# shebon_heart.net
KiCad netlist of a schematic drawn in EAGLE
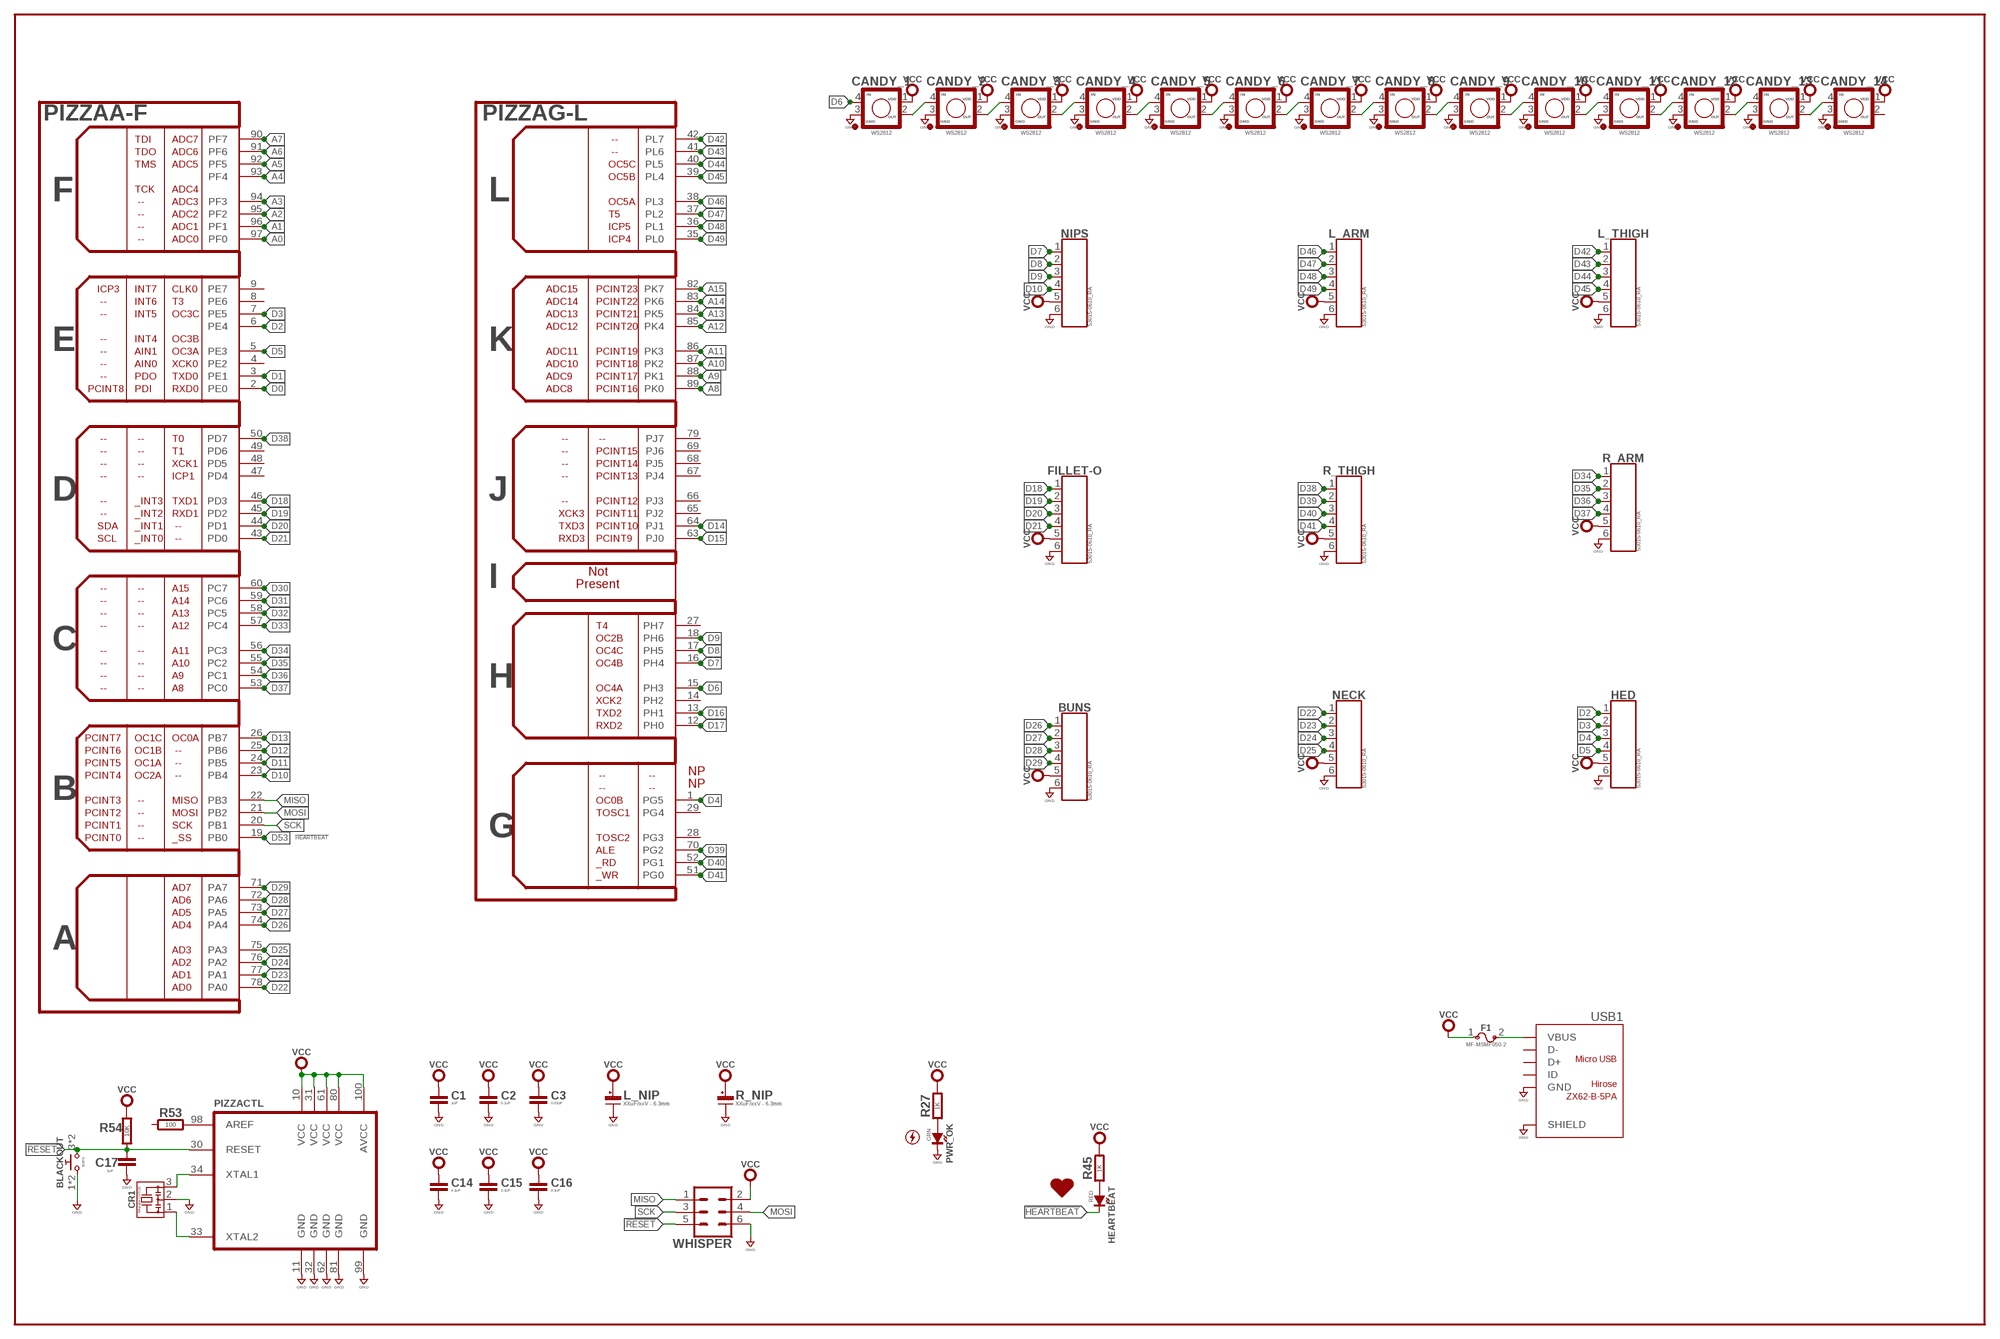
[diagram p0: schematic, sheet 1]

(export (version "E")
  (design (tool "Eeschema 10.0.6"))
  (components
    (comp (ref "BLACKOUT")
      (value "B3FS")
      (footprint "eagle-import:B3FS")
      (libsource (lib "eagle-import") (part "PUSHBTN-MOMB3FS"))
    )
    (comp (ref "BUNS")
      (value "53015-0610_RA")
      (footprint "eagle-import:MICROBLADE-RA-06P")
      (libsource (lib "eagle-import") (part "5301-0610_RA5"))
    )
    (comp (ref "C1")
      (value "1uF")
      (footprint "eagle-import:0603")
      (libsource (lib "eagle-import") (part "CAPACITOR0603"))
    )
    (comp (ref "C2")
      (value "0.1uF")
      (footprint "eagle-import:0603")
      (libsource (lib "eagle-import") (part "CAPACITOR0603"))
    )
    (comp (ref "C3")
      (value "0.01uF")
      (footprint "eagle-import:0603")
      (libsource (lib "eagle-import") (part "CAPACITOR0603"))
    )
    (comp (ref "C14")
      (value "0.1uF")
      (footprint "eagle-import:0603")
      (libsource (lib "eagle-import") (part "CAPACITOR0603"))
    )
    (comp (ref "C15")
      (value "0.1uF")
      (footprint "eagle-import:0603")
      (libsource (lib "eagle-import") (part "CAPACITOR0603"))
    )
    (comp (ref "C16")
      (value "0.1uF")
      (footprint "eagle-import:0603")
      (libsource (lib "eagle-import") (part "CAPACITOR0603"))
    )
    (comp (ref "C17")
      (value "1uF")
      (footprint "eagle-import:0603")
      (libsource (lib "eagle-import") (part "CAPACITOR0603"))
    )
    (comp (ref "CANDY_1")
      (value "WS2812")
      (footprint "eagle-import:NEOPIXEL")
      (libsource (lib "eagle-import") (part "NEOPPIXEL5X5"))
    )
    (comp (ref "CANDY_2")
      (value "WS2812")
      (footprint "eagle-import:NEOPIXEL")
      (libsource (lib "eagle-import") (part "NEOPPIXEL5X5"))
    )
    (comp (ref "CANDY_3")
      (value "WS2812")
      (footprint "eagle-import:NEOPIXEL")
      (libsource (lib "eagle-import") (part "NEOPPIXEL5X5"))
    )
    (comp (ref "CANDY_4")
      (value "WS2812")
      (footprint "eagle-import:NEOPIXEL")
      (libsource (lib "eagle-import") (part "NEOPPIXEL5X5"))
    )
    (comp (ref "CANDY_5")
      (value "WS2812")
      (footprint "eagle-import:NEOPIXEL")
      (libsource (lib "eagle-import") (part "NEOPPIXEL5X5"))
    )
    (comp (ref "CANDY_6")
      (value "WS2812")
      (footprint "eagle-import:NEOPIXEL")
      (libsource (lib "eagle-import") (part "NEOPPIXEL5X5"))
    )
    (comp (ref "CANDY_7")
      (value "WS2812")
      (footprint "eagle-import:NEOPIXEL")
      (libsource (lib "eagle-import") (part "NEOPPIXEL5X5"))
    )
    (comp (ref "CANDY_8")
      (value "WS2812")
      (footprint "eagle-import:NEOPIXEL")
      (libsource (lib "eagle-import") (part "NEOPPIXEL5X5"))
    )
    (comp (ref "CANDY_9")
      (value "WS2812")
      (footprint "eagle-import:NEOPIXEL")
      (libsource (lib "eagle-import") (part "NEOPPIXEL5X5"))
    )
    (comp (ref "CANDY_10")
      (value "WS2812")
      (footprint "eagle-import:NEOPIXEL")
      (libsource (lib "eagle-import") (part "NEOPPIXEL5X5"))
    )
    (comp (ref "CANDY_11")
      (value "WS2812")
      (footprint "eagle-import:NEOPIXEL")
      (libsource (lib "eagle-import") (part "NEOPPIXEL5X5"))
    )
    (comp (ref "CANDY_12")
      (value "WS2812")
      (footprint "eagle-import:NEOPIXEL")
      (libsource (lib "eagle-import") (part "NEOPPIXEL5X5"))
    )
    (comp (ref "CANDY_13")
      (value "WS2812")
      (footprint "eagle-import:NEOPIXEL")
      (libsource (lib "eagle-import") (part "NEOPPIXEL5X5"))
    )
    (comp (ref "CANDY_14")
      (value "WS2812")
      (footprint "eagle-import:NEOPIXEL")
      (libsource (lib "eagle-import") (part "NEOPPIXEL5X5"))
    )
    (comp (ref "CR1")
      (value "Murata CSTCE")
      (footprint "eagle-import:MURATA_CSTCE")
      (libsource (lib "eagle-import") (part "RESONATORMURATA-CSTCE"))
    )
    (comp (ref "F1")
      (value "MF-MSMF050-2")
      (footprint "eagle-import:BOURNS-MF-MSMF")
      (libsource (lib "eagle-import") (part "FUSEBOURNS-MF-MSMF"))
    )
    (comp (ref "FILLET-O")
      (value "53015-0610_RA")
      (footprint "eagle-import:MICROBLADE-RA-06P")
      (libsource (lib "eagle-import") (part "5301-0610_RA5"))
    )
    (comp (ref "HEARTBEAT")
      (value "RED")
      (footprint "eagle-import:SMD_0603")
      (libsource (lib "eagle-import") (part "SMT0603"))
    )
    (comp (ref "HED")
      (value "53015-0610_RA")
      (footprint "eagle-import:MICROBLADE-RA-06P")
      (libsource (lib "eagle-import") (part "5301-0610_RA5"))
    )
    (comp (ref "L_ARM")
      (value "53015-0610_RA")
      (footprint "eagle-import:MICROBLADE-RA-06P")
      (libsource (lib "eagle-import") (part "5301-0610_RA5"))
    )
    (comp (ref "L_NIP")
      (value "XXuF/xxV - 6.3mm")
      (footprint "eagle-import:CAP_ALUM_SMT_6.3")
      (libsource (lib "eagle-import") (part "CAPACITOR_POL-ALUM-SMT-6.3"))
    )
    (comp (ref "L_THIGH")
      (value "53015-0610_RA")
      (footprint "eagle-import:MICROBLADE-RA-06P")
      (libsource (lib "eagle-import") (part "5301-0610_RA5"))
    )
    (comp (ref "NECK")
      (value "53015-0610_RA")
      (footprint "eagle-import:MICROBLADE-RA-06P")
      (libsource (lib "eagle-import") (part "5301-0610_RA5"))
    )
    (comp (ref "NIPS")
      (value "53015-0610_RA")
      (footprint "eagle-import:MICROBLADE-RA-06P")
      (libsource (lib "eagle-import") (part "5301-0610_RA5"))
    )
    (comp (ref "PIZZA")
      (value "ATMEGA-2560")
      (footprint "eagle-import:TQFP-100-A")
      (libsource (lib "eagle-import") (part "ATMEGA-0256"))
    )
    (comp (ref "PWR_OK")
      (value "GRN")
      (footprint "eagle-import:SMD_0603")
      (libsource (lib "eagle-import") (part "SMT0603"))
    )
    (comp (ref "R27")
      (value "1K")
      (footprint "eagle-import:0603")
      (libsource (lib "eagle-import") (part "RESISTOR0603"))
    )
    (comp (ref "R45")
      (value "1K")
      (footprint "eagle-import:0603")
      (libsource (lib "eagle-import") (part "RESISTOR0603"))
    )
    (comp (ref "R53")
      (value "100")
      (footprint "eagle-import:0603")
      (libsource (lib "eagle-import") (part "RESISTOR0603"))
    )
    (comp (ref "R54")
      (value "10K")
      (footprint "eagle-import:0603")
      (libsource (lib "eagle-import") (part "RESISTOR0603"))
    )
    (comp (ref "R_ARM")
      (value "53015-0610_RA")
      (footprint "eagle-import:MICROBLADE-RA-06P")
      (libsource (lib "eagle-import") (part "5301-0610_RA5"))
    )
    (comp (ref "R_NIP")
      (value "XXuF/xxV - 6.3mm")
      (footprint "eagle-import:CAP_ALUM_SMT_6.3")
      (libsource (lib "eagle-import") (part "CAPACITOR_POL-ALUM-SMT-6.3"))
    )
    (comp (ref "R_THIGH")
      (value "53015-0610_RA")
      (footprint "eagle-import:MICROBLADE-RA-06P")
      (libsource (lib "eagle-import") (part "5301-0610_RA5"))
    )
    (comp (ref "U$2")
      (value "ELECTRICITY-050X050MM")
      (footprint "eagle-import:ELECTRICITY-GLYPH-05X05MM")
      (libsource (lib "eagle-import") (part "ELECTRICITY-050X050MM"))
    )
    (comp (ref "U$3")
      (value "HEART-05X04MM")
      (footprint "eagle-import:HEART-GLYPH-05X04MM")
      (libsource (lib "eagle-import") (part "HEART-05X04MM"))
    )
    (comp (ref "USB1")
      (value "ZX62-B-5PA")
      (footprint "eagle-import:MICRO-USB5+6P-SMD-0.65-AB")
      (libsource (lib "eagle-import") (part "MICRO-USB-SMD(ZX62-B-5PA)"))
    )
    (comp (ref "WHISPER")
      (value "MA03-2")
      (footprint "eagle-import:MA03-2")
      (libsource (lib "eagle-import") (part "MA03-2"))
    )
  )
  (nets
    (net (code "1") (name "/~{HEARTBEAT}") (class "Default")
      (node (ref "HEARTBEAT") (pin "K") (pinfunction "C_K") (pintype "passive"))
    )
    (net (code "2") (name "/~{RESET}") (class "Default")
      (node (ref "BLACKOUT") (pin "3") (pinfunction "2_3") (pintype "passive"))
      (node (ref "BLACKOUT") (pin "4") (pinfunction "2_4") (pintype "passive"))
      (node (ref "C17") (pin "1") (pinfunction "1_1") (pintype "passive"))
      (node (ref "PIZZA") (pin "30") (pinfunction "RESET_30") (pintype "input"))
      (node (ref "R54") (pin "2") (pinfunction "2_2") (pintype "passive"))
      (node (ref "WHISPER") (pin "5") (pinfunction "5_5") (pintype "passive"))
    )
    (net (code "3") (name "A0") (class "Default")
      (node (ref "PIZZA") (pin "97") (pinfunction "PF0_97") (pintype "bidirectional"))
    )
    (net (code "4") (name "A1") (class "Default")
      (node (ref "PIZZA") (pin "96") (pinfunction "PF1_96") (pintype "bidirectional"))
    )
    (net (code "5") (name "A2") (class "Default")
      (node (ref "PIZZA") (pin "95") (pinfunction "PF2_95") (pintype "bidirectional"))
    )
    (net (code "6") (name "A3") (class "Default")
      (node (ref "PIZZA") (pin "94") (pinfunction "PF3_94") (pintype "bidirectional"))
    )
    (net (code "7") (name "A4") (class "Default")
      (node (ref "PIZZA") (pin "93") (pinfunction "PF4_93") (pintype "bidirectional"))
    )
    (net (code "8") (name "A5") (class "Default")
      (node (ref "PIZZA") (pin "92") (pinfunction "PF5_92") (pintype "bidirectional"))
    )
    (net (code "9") (name "A6") (class "Default")
      (node (ref "PIZZA") (pin "91") (pinfunction "PF6_91") (pintype "bidirectional"))
    )
    (net (code "10") (name "A7") (class "Default")
      (node (ref "PIZZA") (pin "90") (pinfunction "PF7_90") (pintype "bidirectional"))
    )
    (net (code "11") (name "A8") (class "Default")
      (node (ref "PIZZA") (pin "89") (pinfunction "PK0_89") (pintype "bidirectional"))
    )
    (net (code "12") (name "A9") (class "Default")
      (node (ref "PIZZA") (pin "88") (pinfunction "PK1_88") (pintype "bidirectional"))
    )
    (net (code "13") (name "A10") (class "Default")
      (node (ref "PIZZA") (pin "87") (pinfunction "PK2_87") (pintype "bidirectional"))
    )
    (net (code "14") (name "A11") (class "Default")
      (node (ref "PIZZA") (pin "86") (pinfunction "PK3_86") (pintype "bidirectional"))
    )
    (net (code "15") (name "A12") (class "Default")
      (node (ref "PIZZA") (pin "85") (pinfunction "PK4_85") (pintype "bidirectional"))
    )
    (net (code "16") (name "A13") (class "Default")
      (node (ref "PIZZA") (pin "84") (pinfunction "PK5_84") (pintype "bidirectional"))
    )
    (net (code "17") (name "A14") (class "Default")
      (node (ref "PIZZA") (pin "83") (pinfunction "PK6_83") (pintype "bidirectional"))
    )
    (net (code "18") (name "A15") (class "Default")
      (node (ref "PIZZA") (pin "82") (pinfunction "PK7_82") (pintype "bidirectional"))
    )
    (net (code "19") (name "D0") (class "Default")
      (node (ref "PIZZA") (pin "2") (pinfunction "PE0_2") (pintype "bidirectional"))
    )
    (net (code "20") (name "D1") (class "Default")
      (node (ref "PIZZA") (pin "3") (pinfunction "PE1_3") (pintype "bidirectional"))
    )
    (net (code "21") (name "D2") (class "Default")
      (node (ref "HED") (pin "1") (pinfunction "1_1") (pintype "bidirectional"))
      (node (ref "PIZZA") (pin "6") (pinfunction "PE4_6") (pintype "bidirectional"))
    )
    (net (code "22") (name "D3") (class "Default")
      (node (ref "HED") (pin "2") (pinfunction "2_2") (pintype "bidirectional"))
      (node (ref "PIZZA") (pin "7") (pinfunction "PE5_7") (pintype "bidirectional"))
    )
    (net (code "23") (name "D4") (class "Default")
      (node (ref "HED") (pin "3") (pinfunction "3_3") (pintype "bidirectional"))
      (node (ref "PIZZA") (pin "1") (pinfunction "PG5_1") (pintype "bidirectional"))
    )
    (net (code "24") (name "D5") (class "Default")
      (node (ref "HED") (pin "4") (pinfunction "4_4") (pintype "bidirectional"))
      (node (ref "PIZZA") (pin "5") (pinfunction "PE3_5") (pintype "bidirectional"))
    )
    (net (code "25") (name "D6") (class "Default")
      (node (ref "CANDY_1") (pin "4") (pinfunction "OUT_4") (pintype "bidirectional"))
      (node (ref "PIZZA") (pin "15") (pinfunction "PH3_15") (pintype "bidirectional"))
    )
    (net (code "26") (name "D7") (class "Default")
      (node (ref "NIPS") (pin "1") (pinfunction "1_1") (pintype "bidirectional"))
      (node (ref "PIZZA") (pin "16") (pinfunction "PH4_16") (pintype "bidirectional"))
    )
    (net (code "27") (name "D8") (class "Default")
      (node (ref "NIPS") (pin "2") (pinfunction "2_2") (pintype "bidirectional"))
      (node (ref "PIZZA") (pin "17") (pinfunction "PH5_17") (pintype "bidirectional"))
    )
    (net (code "28") (name "D9") (class "Default")
      (node (ref "NIPS") (pin "3") (pinfunction "3_3") (pintype "bidirectional"))
      (node (ref "PIZZA") (pin "18") (pinfunction "PH6_18") (pintype "bidirectional"))
    )
    (net (code "29") (name "D10") (class "Default")
      (node (ref "NIPS") (pin "4") (pinfunction "4_4") (pintype "bidirectional"))
      (node (ref "PIZZA") (pin "23") (pinfunction "PB4_23") (pintype "bidirectional"))
    )
    (net (code "30") (name "D11") (class "Default")
      (node (ref "PIZZA") (pin "24") (pinfunction "PB5_24") (pintype "bidirectional"))
    )
    (net (code "31") (name "D12") (class "Default")
      (node (ref "PIZZA") (pin "25") (pinfunction "PB6_25") (pintype "bidirectional"))
    )
    (net (code "32") (name "D13") (class "Default")
      (node (ref "PIZZA") (pin "26") (pinfunction "PB7_26") (pintype "bidirectional"))
    )
    (net (code "33") (name "D14") (class "Default")
      (node (ref "PIZZA") (pin "64") (pinfunction "PJ1_64") (pintype "bidirectional"))
    )
    (net (code "34") (name "D15") (class "Default")
      (node (ref "PIZZA") (pin "63") (pinfunction "PJ0_63") (pintype "bidirectional"))
    )
    (net (code "35") (name "D16") (class "Default")
      (node (ref "PIZZA") (pin "13") (pinfunction "PH1_13") (pintype "bidirectional"))
    )
    (net (code "36") (name "D17") (class "Default")
      (node (ref "PIZZA") (pin "12") (pinfunction "PH0_12") (pintype "bidirectional"))
    )
    (net (code "37") (name "D18") (class "Default")
      (node (ref "FILLET-O") (pin "1") (pinfunction "1_1") (pintype "bidirectional"))
      (node (ref "PIZZA") (pin "46") (pinfunction "PD3_46") (pintype "bidirectional"))
    )
    (net (code "38") (name "D19") (class "Default")
      (node (ref "FILLET-O") (pin "2") (pinfunction "2_2") (pintype "bidirectional"))
      (node (ref "PIZZA") (pin "45") (pinfunction "PD2_45") (pintype "bidirectional"))
    )
    (net (code "39") (name "D20") (class "Default")
      (node (ref "FILLET-O") (pin "3") (pinfunction "3_3") (pintype "bidirectional"))
      (node (ref "PIZZA") (pin "44") (pinfunction "PD1_44") (pintype "bidirectional"))
    )
    (net (code "40") (name "D21") (class "Default")
      (node (ref "FILLET-O") (pin "4") (pinfunction "4_4") (pintype "bidirectional"))
      (node (ref "PIZZA") (pin "43") (pinfunction "PD0_43") (pintype "bidirectional"))
    )
    (net (code "41") (name "D22") (class "Default")
      (node (ref "NECK") (pin "1") (pinfunction "1_1") (pintype "bidirectional"))
      (node (ref "PIZZA") (pin "78") (pinfunction "PA0_78") (pintype "bidirectional"))
    )
    (net (code "42") (name "D23") (class "Default")
      (node (ref "NECK") (pin "2") (pinfunction "2_2") (pintype "bidirectional"))
      (node (ref "PIZZA") (pin "77") (pinfunction "PA1_77") (pintype "bidirectional"))
    )
    (net (code "43") (name "D24") (class "Default")
      (node (ref "NECK") (pin "3") (pinfunction "3_3") (pintype "bidirectional"))
      (node (ref "PIZZA") (pin "76") (pinfunction "PA2_76") (pintype "bidirectional"))
    )
    (net (code "44") (name "D25") (class "Default")
      (node (ref "NECK") (pin "4") (pinfunction "4_4") (pintype "bidirectional"))
      (node (ref "PIZZA") (pin "75") (pinfunction "PA3_75") (pintype "bidirectional"))
    )
    (net (code "45") (name "D26") (class "Default")
      (node (ref "BUNS") (pin "1") (pinfunction "1_1") (pintype "bidirectional"))
      (node (ref "PIZZA") (pin "74") (pinfunction "PA4_74") (pintype "bidirectional"))
    )
    (net (code "46") (name "D27") (class "Default")
      (node (ref "BUNS") (pin "2") (pinfunction "2_2") (pintype "bidirectional"))
      (node (ref "PIZZA") (pin "73") (pinfunction "PA5_73") (pintype "bidirectional"))
    )
    (net (code "47") (name "D28") (class "Default")
      (node (ref "BUNS") (pin "3") (pinfunction "3_3") (pintype "bidirectional"))
      (node (ref "PIZZA") (pin "72") (pinfunction "PA6_72") (pintype "bidirectional"))
    )
    (net (code "48") (name "D29") (class "Default")
      (node (ref "BUNS") (pin "4") (pinfunction "4_4") (pintype "bidirectional"))
      (node (ref "PIZZA") (pin "71") (pinfunction "PA7_71") (pintype "bidirectional"))
    )
    (net (code "49") (name "D30") (class "Default")
      (node (ref "PIZZA") (pin "60") (pinfunction "PC7_60") (pintype "bidirectional"))
    )
    (net (code "50") (name "D31") (class "Default")
      (node (ref "PIZZA") (pin "59") (pinfunction "PC6_59") (pintype "bidirectional"))
    )
    (net (code "51") (name "D32") (class "Default")
      (node (ref "PIZZA") (pin "58") (pinfunction "PC5_58") (pintype "bidirectional"))
    )
    (net (code "52") (name "D33") (class "Default")
      (node (ref "PIZZA") (pin "57") (pinfunction "PC4_57") (pintype "bidirectional"))
    )
    (net (code "53") (name "D34") (class "Default")
      (node (ref "PIZZA") (pin "56") (pinfunction "PC3_56") (pintype "bidirectional"))
      (node (ref "R_ARM") (pin "1") (pinfunction "1_1") (pintype "bidirectional"))
    )
    (net (code "54") (name "D35") (class "Default")
      (node (ref "PIZZA") (pin "55") (pinfunction "PC2_55") (pintype "bidirectional"))
      (node (ref "R_ARM") (pin "2") (pinfunction "2_2") (pintype "bidirectional"))
    )
    (net (code "55") (name "D36") (class "Default")
      (node (ref "PIZZA") (pin "54") (pinfunction "PC1_54") (pintype "bidirectional"))
      (node (ref "R_ARM") (pin "3") (pinfunction "3_3") (pintype "bidirectional"))
    )
    (net (code "56") (name "D37") (class "Default")
      (node (ref "PIZZA") (pin "53") (pinfunction "PC0_53") (pintype "bidirectional"))
      (node (ref "R_ARM") (pin "4") (pinfunction "4_4") (pintype "bidirectional"))
    )
    (net (code "57") (name "D38") (class "Default")
      (node (ref "PIZZA") (pin "50") (pinfunction "PD7_50") (pintype "bidirectional"))
      (node (ref "R_THIGH") (pin "1") (pinfunction "1_1") (pintype "bidirectional"))
    )
    (net (code "58") (name "D39") (class "Default")
      (node (ref "PIZZA") (pin "70") (pinfunction "PG2_70") (pintype "bidirectional"))
      (node (ref "R_THIGH") (pin "2") (pinfunction "2_2") (pintype "bidirectional"))
    )
    (net (code "59") (name "D40") (class "Default")
      (node (ref "PIZZA") (pin "52") (pinfunction "PG1_52") (pintype "bidirectional"))
      (node (ref "R_THIGH") (pin "3") (pinfunction "3_3") (pintype "bidirectional"))
    )
    (net (code "60") (name "D41") (class "Default")
      (node (ref "PIZZA") (pin "51") (pinfunction "PG0_51") (pintype "bidirectional"))
      (node (ref "R_THIGH") (pin "4") (pinfunction "4_4") (pintype "bidirectional"))
    )
    (net (code "61") (name "D42") (class "Default")
      (node (ref "L_THIGH") (pin "1") (pinfunction "1_1") (pintype "bidirectional"))
      (node (ref "PIZZA") (pin "42") (pinfunction "PL7_42") (pintype "bidirectional"))
    )
    (net (code "62") (name "D43") (class "Default")
      (node (ref "L_THIGH") (pin "2") (pinfunction "2_2") (pintype "bidirectional"))
      (node (ref "PIZZA") (pin "41") (pinfunction "PL6_41") (pintype "bidirectional"))
    )
    (net (code "63") (name "D44") (class "Default")
      (node (ref "L_THIGH") (pin "3") (pinfunction "3_3") (pintype "bidirectional"))
      (node (ref "PIZZA") (pin "40") (pinfunction "PL5_40") (pintype "bidirectional"))
    )
    (net (code "64") (name "D45") (class "Default")
      (node (ref "L_THIGH") (pin "4") (pinfunction "4_4") (pintype "bidirectional"))
      (node (ref "PIZZA") (pin "39") (pinfunction "PL4_39") (pintype "bidirectional"))
    )
    (net (code "65") (name "D46") (class "Default")
      (node (ref "L_ARM") (pin "1") (pinfunction "1_1") (pintype "bidirectional"))
      (node (ref "PIZZA") (pin "38") (pinfunction "PL3_38") (pintype "bidirectional"))
    )
    (net (code "66") (name "D47") (class "Default")
      (node (ref "L_ARM") (pin "2") (pinfunction "2_2") (pintype "bidirectional"))
      (node (ref "PIZZA") (pin "37") (pinfunction "PL2_37") (pintype "bidirectional"))
    )
    (net (code "67") (name "D48") (class "Default")
      (node (ref "L_ARM") (pin "3") (pinfunction "3_3") (pintype "bidirectional"))
      (node (ref "PIZZA") (pin "36") (pinfunction "PL1_36") (pintype "bidirectional"))
    )
    (net (code "68") (name "D49") (class "Default")
      (node (ref "L_ARM") (pin "4") (pinfunction "4_4") (pintype "bidirectional"))
      (node (ref "PIZZA") (pin "35") (pinfunction "PL0_35") (pintype "bidirectional"))
    )
    (net (code "69") (name "D53") (class "Default")
      (node (ref "PIZZA") (pin "19") (pinfunction "PB0_19") (pintype "bidirectional"))
    )
    (net (code "70") (name "GND") (class "Default")
      (node (ref "BLACKOUT") (pin "1") (pinfunction "1_1") (pintype "passive"))
      (node (ref "BLACKOUT") (pin "2") (pinfunction "1_2") (pintype "passive"))
      (node (ref "BUNS") (pin "6") (pinfunction "6_6") (pintype "bidirectional"))
      (node (ref "C1") (pin "2") (pinfunction "2_2") (pintype "passive"))
      (node (ref "C14") (pin "2") (pinfunction "2_2") (pintype "passive"))
      (node (ref "C15") (pin "2") (pinfunction "2_2") (pintype "passive"))
      (node (ref "C16") (pin "2") (pinfunction "2_2") (pintype "passive"))
      (node (ref "C17") (pin "2") (pinfunction "2_2") (pintype "passive"))
      (node (ref "C2") (pin "2") (pinfunction "2_2") (pintype "passive"))
      (node (ref "C3") (pin "2") (pinfunction "2_2") (pintype "passive"))
      (node (ref "CANDY_1") (pin "3") (pinfunction "GND_3") (pintype "bidirectional"))
      (node (ref "CANDY_10") (pin "3") (pinfunction "GND_3") (pintype "bidirectional"))
      (node (ref "CANDY_11") (pin "3") (pinfunction "GND_3") (pintype "bidirectional"))
      (node (ref "CANDY_12") (pin "3") (pinfunction "GND_3") (pintype "bidirectional"))
      (node (ref "CANDY_13") (pin "3") (pinfunction "GND_3") (pintype "bidirectional"))
      (node (ref "CANDY_14") (pin "3") (pinfunction "GND_3") (pintype "bidirectional"))
      (node (ref "CANDY_2") (pin "3") (pinfunction "GND_3") (pintype "bidirectional"))
      (node (ref "CANDY_3") (pin "3") (pinfunction "GND_3") (pintype "bidirectional"))
      (node (ref "CANDY_4") (pin "3") (pinfunction "GND_3") (pintype "bidirectional"))
      (node (ref "CANDY_5") (pin "3") (pinfunction "GND_3") (pintype "bidirectional"))
      (node (ref "CANDY_6") (pin "3") (pinfunction "GND_3") (pintype "bidirectional"))
      (node (ref "CANDY_7") (pin "3") (pinfunction "GND_3") (pintype "bidirectional"))
      (node (ref "CANDY_8") (pin "3") (pinfunction "GND_3") (pintype "bidirectional"))
      (node (ref "CANDY_9") (pin "3") (pinfunction "GND_3") (pintype "bidirectional"))
      (node (ref "CR1") (pin "2") (pinfunction "2_2") (pintype "bidirectional"))
      (node (ref "FILLET-O") (pin "6") (pinfunction "6_6") (pintype "bidirectional"))
      (node (ref "HED") (pin "6") (pinfunction "6_6") (pintype "bidirectional"))
      (node (ref "L_ARM") (pin "6") (pinfunction "6_6") (pintype "bidirectional"))
      (node (ref "L_NIP") (pin "-") (pinfunction "N_-") (pintype "bidirectional"))
      (node (ref "L_THIGH") (pin "6") (pinfunction "6_6") (pintype "bidirectional"))
      (node (ref "NECK") (pin "6") (pinfunction "6_6") (pintype "bidirectional"))
      (node (ref "NIPS") (pin "6") (pinfunction "6_6") (pintype "bidirectional"))
      (node (ref "PIZZA") (pin "11") (pinfunction "GND_11") (pintype "power_in"))
      (node (ref "PIZZA") (pin "32") (pinfunction "GND_32") (pintype "power_in"))
      (node (ref "PIZZA") (pin "62") (pinfunction "GND_62") (pintype "power_in"))
      (node (ref "PIZZA") (pin "81") (pinfunction "GND_81") (pintype "power_in"))
      (node (ref "PIZZA") (pin "99") (pinfunction "GND_99") (pintype "power_in"))
      (node (ref "PWR_OK") (pin "K") (pinfunction "C_K") (pintype "passive"))
      (node (ref "R_ARM") (pin "6") (pinfunction "6_6") (pintype "bidirectional"))
      (node (ref "R_NIP") (pin "-") (pinfunction "N_-") (pintype "bidirectional"))
      (node (ref "R_THIGH") (pin "6") (pinfunction "6_6") (pintype "bidirectional"))
      (node (ref "USB1") (pin "5") (pinfunction "GND_5") (pintype "power_in"))
      (node (ref "USB1") (pin "P1") (pinfunction "SHIELD_P1") (pintype "power_in"))
      (node (ref "USB1") (pin "P2") (pinfunction "SHIELD_P2") (pintype "power_in"))
      (node (ref "USB1") (pin "P3_1") (pinfunction "SHIELD_P3_1") (pintype "power_in"))
      (node (ref "USB1") (pin "P3_2") (pinfunction "SHIELD_P3_2") (pintype "power_in"))
      (node (ref "USB1") (pin "P3_3") (pinfunction "SHIELD_P3_3") (pintype "power_in"))
      (node (ref "USB1") (pin "P4_1") (pinfunction "SHIELD_P4_1") (pintype "power_in"))
      (node (ref "USB1") (pin "P4_2") (pinfunction "SHIELD_P4_2") (pintype "power_in"))
      (node (ref "USB1") (pin "P4_3") (pinfunction "SHIELD_P4_3") (pintype "power_in"))
      (node (ref "USB1") (pin "P5") (pinfunction "SHIELD_P5") (pintype "power_in"))
      (node (ref "USB1") (pin "P6") (pinfunction "SHIELD_P6") (pintype "power_in"))
      (node (ref "WHISPER") (pin "6") (pinfunction "6_6") (pintype "passive"))
    )
    (net (code "71") (name "MISO") (class "Default")
      (node (ref "PIZZA") (pin "22") (pinfunction "PB3_22") (pintype "bidirectional"))
      (node (ref "WHISPER") (pin "1") (pinfunction "1_1") (pintype "passive"))
    )
    (net (code "72") (name "MOSI") (class "Default")
      (node (ref "PIZZA") (pin "21") (pinfunction "PB2_21") (pintype "bidirectional"))
      (node (ref "WHISPER") (pin "4") (pinfunction "4_4") (pintype "passive"))
    )
    (net (code "73") (name "Net-(CANDY_1-IN)") (class "Default")
      (node (ref "CANDY_1") (pin "2") (pinfunction "IN_2") (pintype "bidirectional"))
      (node (ref "CANDY_2") (pin "4") (pinfunction "OUT_4") (pintype "bidirectional"))
    )
    (net (code "74") (name "Net-(CANDY_2-IN)") (class "Default")
      (node (ref "CANDY_2") (pin "2") (pinfunction "IN_2") (pintype "bidirectional"))
      (node (ref "CANDY_3") (pin "4") (pinfunction "OUT_4") (pintype "bidirectional"))
    )
    (net (code "75") (name "Net-(CANDY_3-IN)") (class "Default")
      (node (ref "CANDY_3") (pin "2") (pinfunction "IN_2") (pintype "bidirectional"))
      (node (ref "CANDY_4") (pin "4") (pinfunction "OUT_4") (pintype "bidirectional"))
    )
    (net (code "76") (name "Net-(CANDY_4-IN)") (class "Default")
      (node (ref "CANDY_4") (pin "2") (pinfunction "IN_2") (pintype "bidirectional"))
      (node (ref "CANDY_5") (pin "4") (pinfunction "OUT_4") (pintype "bidirectional"))
    )
    (net (code "77") (name "Net-(CANDY_5-IN)") (class "Default")
      (node (ref "CANDY_5") (pin "2") (pinfunction "IN_2") (pintype "bidirectional"))
      (node (ref "CANDY_6") (pin "4") (pinfunction "OUT_4") (pintype "bidirectional"))
    )
    (net (code "78") (name "Net-(CANDY_6-IN)") (class "Default")
      (node (ref "CANDY_6") (pin "2") (pinfunction "IN_2") (pintype "bidirectional"))
      (node (ref "CANDY_7") (pin "4") (pinfunction "OUT_4") (pintype "bidirectional"))
    )
    (net (code "79") (name "Net-(CANDY_7-IN)") (class "Default")
      (node (ref "CANDY_7") (pin "2") (pinfunction "IN_2") (pintype "bidirectional"))
      (node (ref "CANDY_8") (pin "4") (pinfunction "OUT_4") (pintype "bidirectional"))
    )
    (net (code "80") (name "Net-(CANDY_8-IN)") (class "Default")
      (node (ref "CANDY_8") (pin "2") (pinfunction "IN_2") (pintype "bidirectional"))
      (node (ref "CANDY_9") (pin "4") (pinfunction "OUT_4") (pintype "bidirectional"))
    )
    (net (code "81") (name "Net-(CANDY_10-IN)") (class "Default")
      (node (ref "CANDY_10") (pin "2") (pinfunction "IN_2") (pintype "bidirectional"))
      (node (ref "CANDY_11") (pin "4") (pinfunction "OUT_4") (pintype "bidirectional"))
    )
    (net (code "82") (name "Net-(CANDY_10-OUT)") (class "Default")
      (node (ref "CANDY_10") (pin "4") (pinfunction "OUT_4") (pintype "bidirectional"))
      (node (ref "CANDY_9") (pin "2") (pinfunction "IN_2") (pintype "bidirectional"))
    )
    (net (code "83") (name "Net-(CANDY_11-IN)") (class "Default")
      (node (ref "CANDY_11") (pin "2") (pinfunction "IN_2") (pintype "bidirectional"))
      (node (ref "CANDY_12") (pin "4") (pinfunction "OUT_4") (pintype "bidirectional"))
    )
    (net (code "84") (name "Net-(CANDY_12-IN)") (class "Default")
      (node (ref "CANDY_12") (pin "2") (pinfunction "IN_2") (pintype "bidirectional"))
      (node (ref "CANDY_13") (pin "4") (pinfunction "OUT_4") (pintype "bidirectional"))
    )
    (net (code "85") (name "Net-(CANDY_13-IN)") (class "Default")
      (node (ref "CANDY_13") (pin "2") (pinfunction "IN_2") (pintype "bidirectional"))
      (node (ref "CANDY_14") (pin "4") (pinfunction "OUT_4") (pintype "bidirectional"))
    )
    (net (code "86") (name "Net-(HEARTBEAT-PadA)") (class "Default")
      (node (ref "HEARTBEAT") (pin "A") (pinfunction "A_A") (pintype "passive"))
      (node (ref "R45") (pin "1") (pinfunction "1_1") (pintype "passive"))
    )
    (net (code "87") (name "Net-(PIZZAB-AREF)") (class "Default")
      (node (ref "PIZZA") (pin "98") (pinfunction "AREF_98") (pintype "input"))
      (node (ref "R53") (pin "2") (pinfunction "2_2") (pintype "passive"))
    )
    (net (code "88") (name "Net-(PIZZAB-XTAL1)") (class "Default")
      (node (ref "CR1") (pin "3") (pinfunction "3_3") (pintype "bidirectional"))
      (node (ref "PIZZA") (pin "34") (pinfunction "XTAL1_34") (pintype "passive"))
    )
    (net (code "89") (name "Net-(PIZZAB-XTAL2)") (class "Default")
      (node (ref "CR1") (pin "1") (pinfunction "1_1") (pintype "bidirectional"))
      (node (ref "PIZZA") (pin "33") (pinfunction "XTAL2_33") (pintype "passive"))
    )
    (net (code "90") (name "Net-(PWR_OK-PadA)") (class "Default")
      (node (ref "PWR_OK") (pin "A") (pinfunction "A_A") (pintype "passive"))
      (node (ref "R27") (pin "1") (pinfunction "1_1") (pintype "passive"))
    )
    (net (code "91") (name "Net-(USB1-VBUS)") (class "Default")
      (node (ref "F1") (pin "2") (pinfunction "2_2") (pintype "bidirectional"))
      (node (ref "USB1") (pin "1") (pinfunction "VBUS_1") (pintype "power_in"))
    )
    (net (code "92") (name "SCK") (class "Default")
      (node (ref "PIZZA") (pin "20") (pinfunction "PB1_20") (pintype "bidirectional"))
      (node (ref "WHISPER") (pin "3") (pinfunction "3_3") (pintype "passive"))
    )
    (net (code "93") (name "VCC") (class "Default")
      (node (ref "BUNS") (pin "5") (pinfunction "5_5") (pintype "bidirectional"))
      (node (ref "C1") (pin "1") (pinfunction "1_1") (pintype "passive"))
      (node (ref "C14") (pin "1") (pinfunction "1_1") (pintype "passive"))
      (node (ref "C15") (pin "1") (pinfunction "1_1") (pintype "passive"))
      (node (ref "C16") (pin "1") (pinfunction "1_1") (pintype "passive"))
      (node (ref "C2") (pin "1") (pinfunction "1_1") (pintype "passive"))
      (node (ref "C3") (pin "1") (pinfunction "1_1") (pintype "passive"))
      (node (ref "CANDY_1") (pin "1") (pinfunction "VDD_1") (pintype "bidirectional"))
      (node (ref "CANDY_10") (pin "1") (pinfunction "VDD_1") (pintype "bidirectional"))
      (node (ref "CANDY_11") (pin "1") (pinfunction "VDD_1") (pintype "bidirectional"))
      (node (ref "CANDY_12") (pin "1") (pinfunction "VDD_1") (pintype "bidirectional"))
      (node (ref "CANDY_13") (pin "1") (pinfunction "VDD_1") (pintype "bidirectional"))
      (node (ref "CANDY_14") (pin "1") (pinfunction "VDD_1") (pintype "bidirectional"))
      (node (ref "CANDY_2") (pin "1") (pinfunction "VDD_1") (pintype "bidirectional"))
      (node (ref "CANDY_3") (pin "1") (pinfunction "VDD_1") (pintype "bidirectional"))
      (node (ref "CANDY_4") (pin "1") (pinfunction "VDD_1") (pintype "bidirectional"))
      (node (ref "CANDY_5") (pin "1") (pinfunction "VDD_1") (pintype "bidirectional"))
      (node (ref "CANDY_6") (pin "1") (pinfunction "VDD_1") (pintype "bidirectional"))
      (node (ref "CANDY_7") (pin "1") (pinfunction "VDD_1") (pintype "bidirectional"))
      (node (ref "CANDY_8") (pin "1") (pinfunction "VDD_1") (pintype "bidirectional"))
      (node (ref "CANDY_9") (pin "1") (pinfunction "VDD_1") (pintype "bidirectional"))
      (node (ref "F1") (pin "1") (pinfunction "1_1") (pintype "bidirectional"))
      (node (ref "FILLET-O") (pin "5") (pinfunction "5_5") (pintype "bidirectional"))
      (node (ref "HED") (pin "5") (pinfunction "5_5") (pintype "bidirectional"))
      (node (ref "L_ARM") (pin "5") (pinfunction "5_5") (pintype "bidirectional"))
      (node (ref "L_NIP") (pin "+") (pinfunction "P_+") (pintype "bidirectional"))
      (node (ref "L_THIGH") (pin "5") (pinfunction "5_5") (pintype "bidirectional"))
      (node (ref "NECK") (pin "5") (pinfunction "5_5") (pintype "bidirectional"))
      (node (ref "NIPS") (pin "5") (pinfunction "5_5") (pintype "bidirectional"))
      (node (ref "PIZZA") (pin "10") (pinfunction "VCC_10") (pintype "power_in"))
      (node (ref "PIZZA") (pin "100") (pinfunction "AVCC_100") (pintype "power_in"))
      (node (ref "PIZZA") (pin "31") (pinfunction "VCC_31") (pintype "power_in"))
      (node (ref "PIZZA") (pin "61") (pinfunction "VCC_61") (pintype "power_in"))
      (node (ref "PIZZA") (pin "80") (pinfunction "VCC_80") (pintype "power_in"))
      (node (ref "R27") (pin "2") (pinfunction "2_2") (pintype "passive"))
      (node (ref "R45") (pin "2") (pinfunction "2_2") (pintype "passive"))
      (node (ref "R54") (pin "1") (pinfunction "1_1") (pintype "passive"))
      (node (ref "R_ARM") (pin "5") (pinfunction "5_5") (pintype "bidirectional"))
      (node (ref "R_NIP") (pin "+") (pinfunction "P_+") (pintype "bidirectional"))
      (node (ref "R_THIGH") (pin "5") (pinfunction "5_5") (pintype "bidirectional"))
      (node (ref "WHISPER") (pin "2") (pinfunction "2_2") (pintype "passive"))
    )
    (net (code "94") (name "unconnected-(CANDY_14-IN-Pad2)") (class "Default")
      (node (ref "CANDY_14") (pin "2") (pinfunction "IN_2") (pintype "bidirectional"))
    )
    (net (code "95") (name "unconnected-(PIZZAA-PD4-Pad47)") (class "Default")
      (node (ref "PIZZA") (pin "47") (pinfunction "PD4_47") (pintype "bidirectional"))
    )
    (net (code "96") (name "unconnected-(PIZZAA-PD5-Pad48)") (class "Default")
      (node (ref "PIZZA") (pin "48") (pinfunction "PD5_48") (pintype "bidirectional"))
    )
    (net (code "97") (name "unconnected-(PIZZAA-PD6-Pad49)") (class "Default")
      (node (ref "PIZZA") (pin "49") (pinfunction "PD6_49") (pintype "bidirectional"))
    )
    (net (code "98") (name "unconnected-(PIZZAA-PE2-Pad4)") (class "Default")
      (node (ref "PIZZA") (pin "4") (pinfunction "PE2_4") (pintype "bidirectional"))
    )
    (net (code "99") (name "unconnected-(PIZZAA-PE6-Pad8)") (class "Default")
      (node (ref "PIZZA") (pin "8") (pinfunction "PE6_8") (pintype "bidirectional"))
    )
    (net (code "100") (name "unconnected-(PIZZAA-PE7-Pad9)") (class "Default")
      (node (ref "PIZZA") (pin "9") (pinfunction "PE7_9") (pintype "bidirectional"))
    )
    (net (code "101") (name "unconnected-(PIZZAC-PG3-Pad28)") (class "Default")
      (node (ref "PIZZA") (pin "28") (pinfunction "PG3_28") (pintype "bidirectional"))
    )
    (net (code "102") (name "unconnected-(PIZZAC-PG4-Pad29)") (class "Default")
      (node (ref "PIZZA") (pin "29") (pinfunction "PG4_29") (pintype "bidirectional"))
    )
    (net (code "103") (name "unconnected-(PIZZAC-PH2-Pad14)") (class "Default")
      (node (ref "PIZZA") (pin "14") (pinfunction "PH2_14") (pintype "bidirectional"))
    )
    (net (code "104") (name "unconnected-(PIZZAC-PH7-Pad27)") (class "Default")
      (node (ref "PIZZA") (pin "27") (pinfunction "PH7_27") (pintype "bidirectional"))
    )
    (net (code "105") (name "unconnected-(PIZZAC-PJ2-Pad65)") (class "Default")
      (node (ref "PIZZA") (pin "65") (pinfunction "PJ2_65") (pintype "bidirectional"))
    )
    (net (code "106") (name "unconnected-(PIZZAC-PJ3-Pad66)") (class "Default")
      (node (ref "PIZZA") (pin "66") (pinfunction "PJ3_66") (pintype "bidirectional"))
    )
    (net (code "107") (name "unconnected-(PIZZAC-PJ4-Pad67)") (class "Default")
      (node (ref "PIZZA") (pin "67") (pinfunction "PJ4_67") (pintype "bidirectional"))
    )
    (net (code "108") (name "unconnected-(PIZZAC-PJ5-Pad68)") (class "Default")
      (node (ref "PIZZA") (pin "68") (pinfunction "PJ5_68") (pintype "bidirectional"))
    )
    (net (code "109") (name "unconnected-(PIZZAC-PJ6-Pad69)") (class "Default")
      (node (ref "PIZZA") (pin "69") (pinfunction "PJ6_69") (pintype "bidirectional"))
    )
    (net (code "110") (name "unconnected-(PIZZAC-PJ7-Pad79)") (class "Default")
      (node (ref "PIZZA") (pin "79") (pinfunction "PJ7_79") (pintype "bidirectional"))
    )
    (net (code "111") (name "unconnected-(R53-Pad1)") (class "Default")
      (node (ref "R53") (pin "1") (pinfunction "1_1") (pintype "passive"))
    )
    (net (code "112") (name "unconnected-(USB1-D+-Pad3)") (class "Default")
      (node (ref "USB1") (pin "3") (pinfunction "D+_3") (pintype "bidirectional"))
    )
    (net (code "113") (name "unconnected-(USB1-D--Pad2)") (class "Default")
      (node (ref "USB1") (pin "2") (pinfunction "D-_2") (pintype "bidirectional"))
    )
    (net (code "114") (name "unconnected-(USB1-ID-Pad4)") (class "Default")
      (node (ref "USB1") (pin "4") (pinfunction "ID_4") (pintype "bidirectional"))
    )
  )
)
